# nintendac_mini.net
KiCad netlist of a schematic drawn in EAGLE
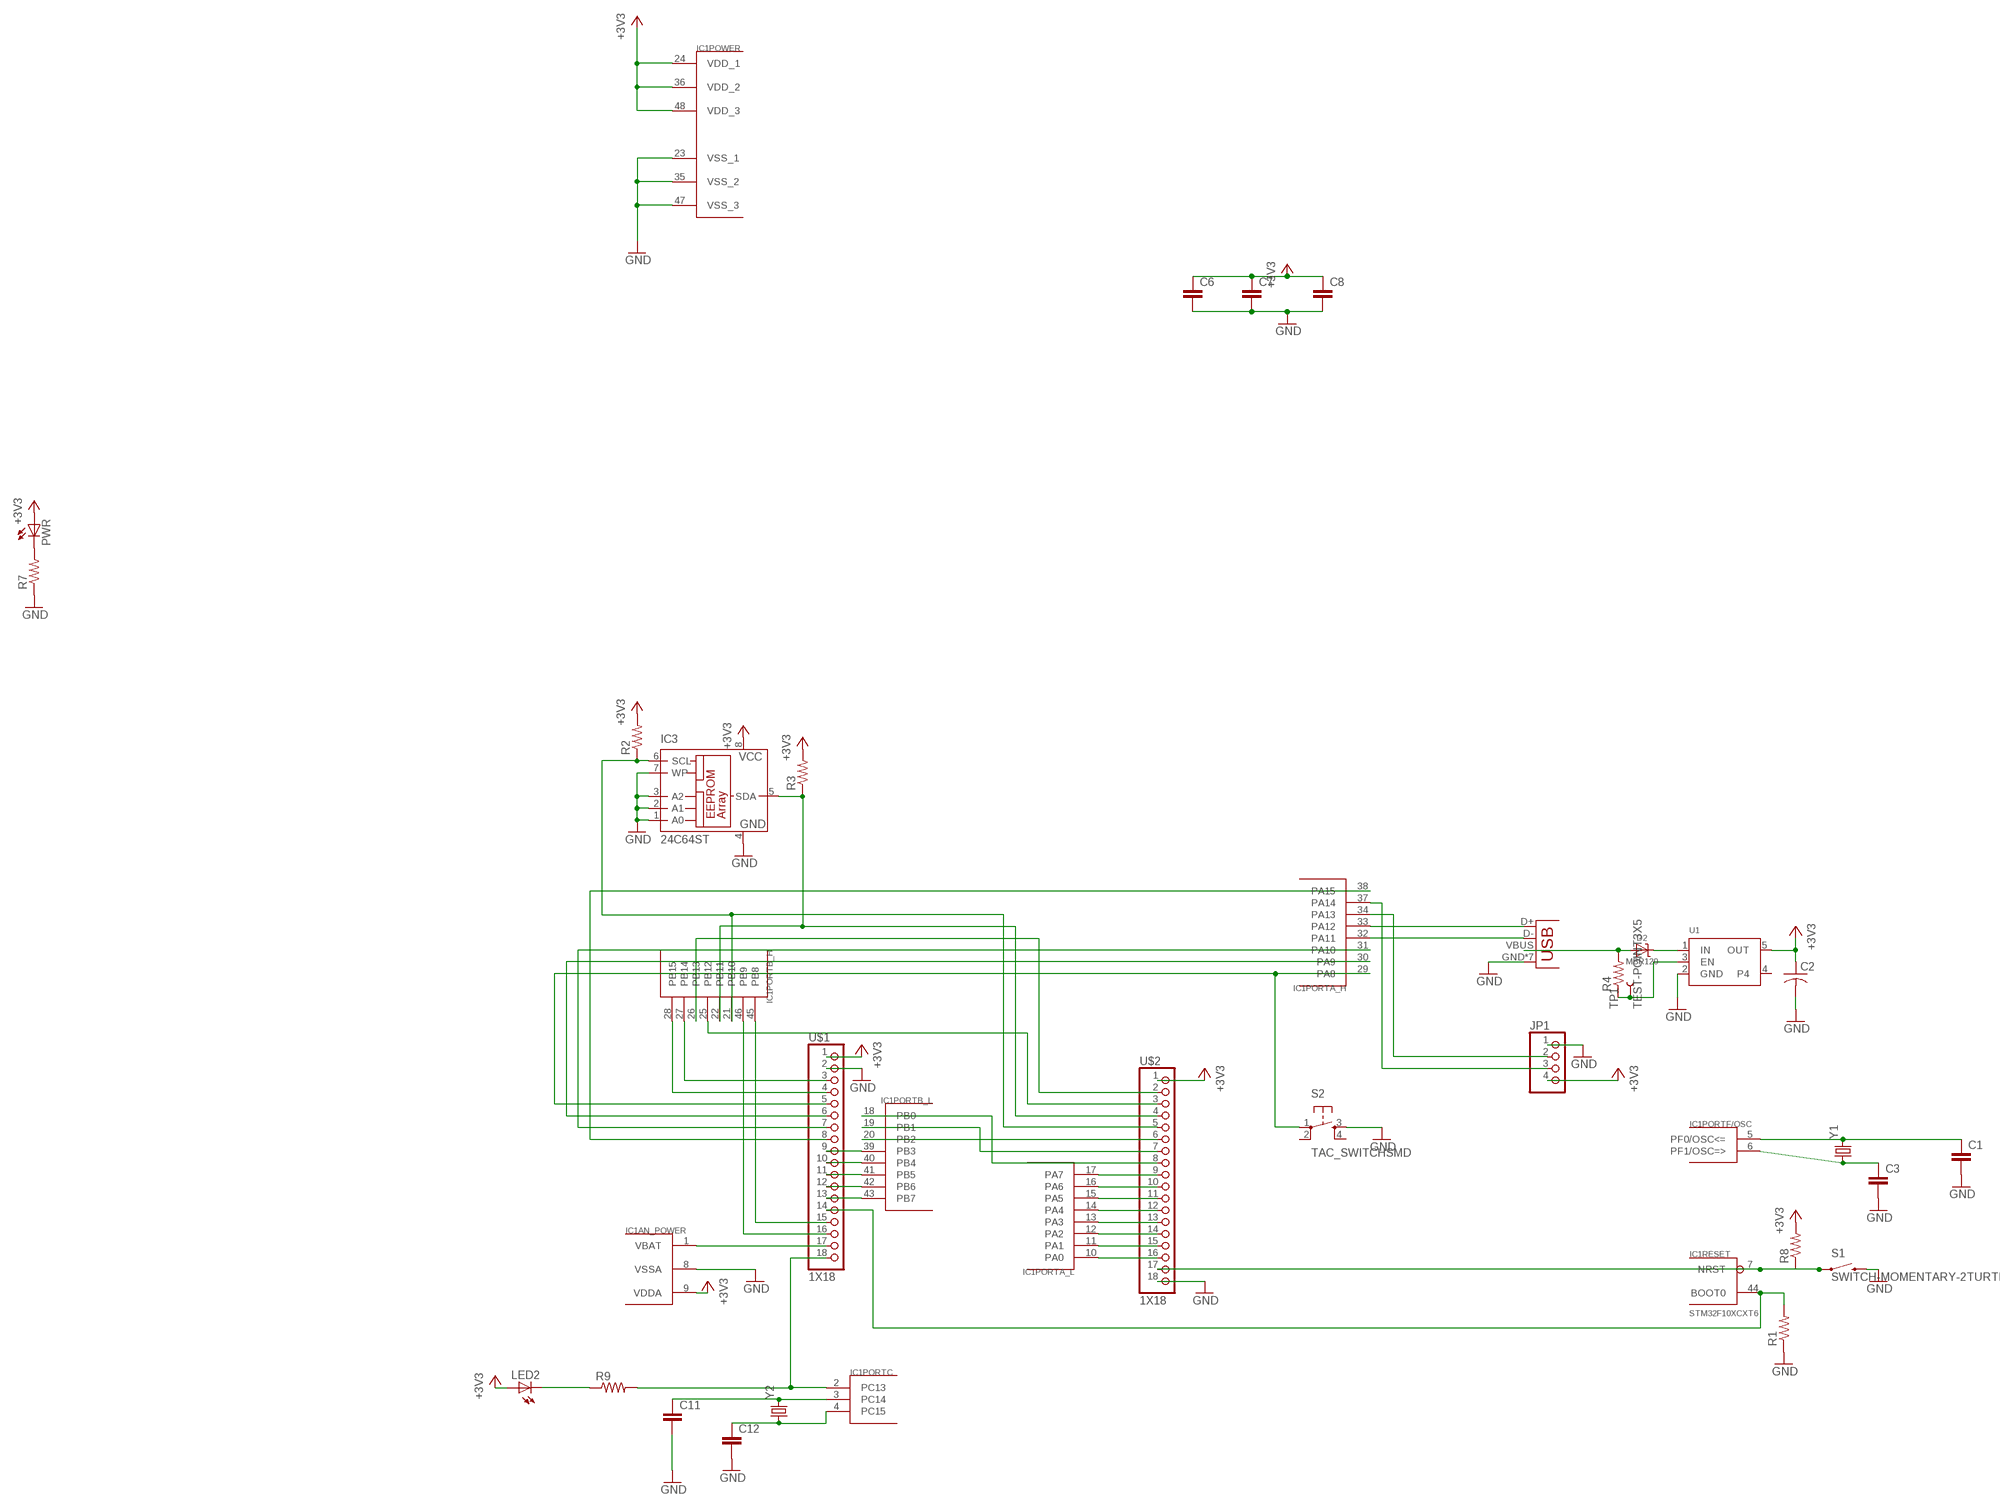
[diagram p0: schematic, sheet 1]

(export (version "E")
  (design (tool "Eeschema 10.0.6"))
  (components
    (comp (ref "C1")
      (value "CAP0805")
      (footprint "eagle-import:0805")
      (libsource (lib "eagle-import") (part "CAP0805"))
    )
    (comp (ref "C2")
      (value "C-USC1210")
      (footprint "eagle-import:C1210")
      (libsource (lib "eagle-import") (part "C-USC1210"))
    )
    (comp (ref "C3")
      (value "CAP0805")
      (footprint "eagle-import:0805")
      (libsource (lib "eagle-import") (part "CAP0805"))
    )
    (comp (ref "C6")
      (value "CAP0805")
      (footprint "eagle-import:0805")
      (libsource (lib "eagle-import") (part "CAP0805"))
    )
    (comp (ref "C7")
      (value "CAP0805")
      (footprint "eagle-import:0805")
      (libsource (lib "eagle-import") (part "CAP0805"))
    )
    (comp (ref "C8")
      (value "CAP0805")
      (footprint "eagle-import:0805")
      (libsource (lib "eagle-import") (part "CAP0805"))
    )
    (comp (ref "C11")
      (value "CAP0805")
      (footprint "eagle-import:0805")
      (libsource (lib "eagle-import") (part "CAP0805"))
    )
    (comp (ref "C12")
      (value "CAP0805")
      (footprint "eagle-import:0805")
      (libsource (lib "eagle-import") (part "CAP0805"))
    )
    (comp (ref "D2")
      (value "MBR120")
      (footprint "eagle-import:SOD-123")
      (libsource (lib "eagle-import") (part "DIODE-SCHOTTKYSOD-123"))
    )
    (comp (ref "IC1")
      (value "STM32F10XCXT6")
      (footprint "eagle-import:TQFP48")
      (libsource (lib "eagle-import") (part "STM32F10XCXT6"))
    )
    (comp (ref "IC3")
      (value "24C64ST")
      (footprint "eagle-import:TSSOP8")
      (fields (field (name "MPN") "CAT24C64YI-GT3"))
      (libsource (lib "eagle-import") (part "24STC64"))
    )
    (comp (ref "JP1")
      (value "PINHD-1X4")
      (footprint "eagle-import:1X04")
      (libsource (lib "eagle-import") (part "PINHD-1X4"))
    )
    (comp (ref "LED2")
      (value "LEDCHIP-LED0805")
      (footprint "eagle-import:CHIP-LED0805")
      (libsource (lib "eagle-import") (part "LEDCHIP-LED0805"))
    )
    (comp (ref "PWR")
      (value "LEDCHIP-LED0805")
      (footprint "eagle-import:CHIP-LED0805")
      (libsource (lib "eagle-import") (part "LEDCHIP-LED0805"))
    )
    (comp (ref "R1")
      (value "RESISTOR0805-RES")
      (footprint "eagle-import:0805")
      (libsource (lib "eagle-import") (part "RESISTOR0805-RES"))
    )
    (comp (ref "R2")
      (value "RESISTOR0805-RES")
      (footprint "eagle-import:0805")
      (libsource (lib "eagle-import") (part "RESISTOR0805-RES"))
    )
    (comp (ref "R3")
      (value "RESISTOR0805-RES")
      (footprint "eagle-import:0805")
      (libsource (lib "eagle-import") (part "RESISTOR0805-RES"))
    )
    (comp (ref "R4")
      (value "RESISTOR0805-RES")
      (footprint "eagle-import:0805")
      (libsource (lib "eagle-import") (part "RESISTOR0805-RES"))
    )
    (comp (ref "R7")
      (value "RESISTOR0805-RES")
      (footprint "eagle-import:0805")
      (libsource (lib "eagle-import") (part "RESISTOR0805-RES"))
    )
    (comp (ref "R8")
      (value "RESISTOR0805-RES")
      (footprint "eagle-import:0805")
      (libsource (lib "eagle-import") (part "RESISTOR0805-RES"))
    )
    (comp (ref "R9")
      (value "RESISTOR0805-RES")
      (footprint "eagle-import:0805")
      (libsource (lib "eagle-import") (part "RESISTOR0805-RES"))
    )
    (comp (ref "S1")
      (value "SWITCH-MOMENTARY-2TURTLE")
      (footprint "eagle-import:KMR2")
      (libsource (lib "eagle-import") (part "SWITCH-MOMENTARY-2TURTLE"))
    )
    (comp (ref "S2")
      (value "TAC_SWITCHSMD")
      (footprint "eagle-import:TACTILE-SWITCH-SMD")
      (libsource (lib "eagle-import") (part "TAC_SWITCHSMD"))
    )
    (comp (ref "TP1")
      (value "TEST-POINT3X5")
      (footprint "eagle-import:PAD.03X.05")
      (libsource (lib "eagle-import") (part "TEST-POINT3X5"))
    )
    (comp (ref "U$1")
      (value "1X18")
      (footprint "eagle-import:1X18")
      (libsource (lib "eagle-import") (part "1X18"))
    )
    (comp (ref "U$2")
      (value "1X18")
      (footprint "eagle-import:1X18")
      (libsource (lib "eagle-import") (part "1X18"))
    )
    (comp (ref "U1")
      (value "VREG_SOT23-5")
      (footprint "eagle-import:SOT23-5")
      (libsource (lib "eagle-import") (part "VREG_SOT23-5"))
    )
    (comp (ref "X1")
      (value "USB-MICROB")
      (footprint "eagle-import:USB-MICROB")
      (libsource (lib "eagle-import") (part "USB-MICROB"))
    )
    (comp (ref "Y1")
      (value "CRYSTALHC49US")
      (footprint "eagle-import:HC49US")
      (libsource (lib "eagle-import") (part "CRYSTALHC49US"))
    )
    (comp (ref "Y2")
      (value "CRYSTALTC26H_EZ")
      (footprint "eagle-import:TC26HEZ")
      (libsource (lib "eagle-import") (part "CRYSTALTC26H_EZ"))
    )
  )
  (nets
    (net (code "1") (name "+3V3") (class "Default")
      (node (ref "C2") (pin "1") (pinfunction "1_1") (pintype "passive"))
      (node (ref "C6") (pin "1") (pinfunction "1_1") (pintype "passive"))
      (node (ref "C7") (pin "1") (pinfunction "1_1") (pintype "passive"))
      (node (ref "C8") (pin "1") (pinfunction "1_1") (pintype "passive"))
      (node (ref "IC1") (pin "24") (pinfunction "VDD_1_24") (pintype "power_in"))
      (node (ref "IC1") (pin "36") (pinfunction "VDD_2_36") (pintype "power_in"))
      (node (ref "IC1") (pin "48") (pinfunction "VDD_3_48") (pintype "power_in"))
      (node (ref "IC1") (pin "9") (pinfunction "VDDA_9") (pintype "power_in"))
      (node (ref "IC3") (pin "8") (pinfunction "VCC_8") (pintype "power_in"))
      (node (ref "JP1") (pin "4") (pinfunction "4_4") (pintype "passive"))
      (node (ref "LED2") (pin "A") (pinfunction "A_A") (pintype "passive"))
      (node (ref "PWR") (pin "A") (pinfunction "A_A") (pintype "passive"))
      (node (ref "R2") (pin "2") (pinfunction "2_2") (pintype "passive"))
      (node (ref "R3") (pin "2") (pinfunction "2_2") (pintype "passive"))
      (node (ref "R8") (pin "2") (pinfunction "2_2") (pintype "passive"))
      (node (ref "U$1") (pin "1") (pinfunction "1_1") (pintype "passive"))
      (node (ref "U$2") (pin "1") (pinfunction "1_1") (pintype "passive"))
      (node (ref "U1") (pin "5") (pinfunction "OUT_5") (pintype "power_in"))
    )
    (net (code "2") (name "GND") (class "Default")
      (node (ref "C1") (pin "2") (pinfunction "2_2") (pintype "passive"))
      (node (ref "C11") (pin "2") (pinfunction "2_2") (pintype "passive"))
      (node (ref "C12") (pin "2") (pinfunction "2_2") (pintype "passive"))
      (node (ref "C2") (pin "2") (pinfunction "2_2") (pintype "passive"))
      (node (ref "C3") (pin "2") (pinfunction "2_2") (pintype "passive"))
      (node (ref "C6") (pin "2") (pinfunction "2_2") (pintype "passive"))
      (node (ref "C7") (pin "2") (pinfunction "2_2") (pintype "passive"))
      (node (ref "C8") (pin "2") (pinfunction "2_2") (pintype "passive"))
      (node (ref "IC1") (pin "23") (pinfunction "VSS_1_23") (pintype "power_in"))
      (node (ref "IC1") (pin "35") (pinfunction "VSS_2_35") (pintype "power_in"))
      (node (ref "IC1") (pin "47") (pinfunction "VSS_3_47") (pintype "power_in"))
      (node (ref "IC1") (pin "8") (pinfunction "VSSA_8") (pintype "power_in"))
      (node (ref "IC3") (pin "1") (pinfunction "A0_1") (pintype "input"))
      (node (ref "IC3") (pin "2") (pinfunction "A1_2") (pintype "input"))
      (node (ref "IC3") (pin "3") (pinfunction "A2_3") (pintype "input"))
      (node (ref "IC3") (pin "4") (pinfunction "GND_4") (pintype "power_in"))
      (node (ref "IC3") (pin "7") (pinfunction "WP_7") (pintype "input"))
      (node (ref "JP1") (pin "1") (pinfunction "1_1") (pintype "passive"))
      (node (ref "R1") (pin "1") (pinfunction "1_1") (pintype "passive"))
      (node (ref "R7") (pin "1") (pinfunction "1_1") (pintype "passive"))
      (node (ref "S1") (pin "3") (pinfunction "2_3") (pintype "passive"))
      (node (ref "S2") (pin "3") (pinfunction "3_3") (pintype "passive"))
      (node (ref "U$1") (pin "2") (pinfunction "2_2") (pintype "passive"))
      (node (ref "U$2") (pin "18") (pinfunction "18_18") (pintype "passive"))
      (node (ref "U1") (pin "2") (pinfunction "GND_2") (pintype "power_in"))
      (node (ref "X1") (pin "GND") (pinfunction "GND_GND") (pintype "bidirectional"))
      (node (ref "X1") (pin "P1") (pinfunction "GND_P1") (pintype "bidirectional"))
      (node (ref "X1") (pin "P2") (pinfunction "GND_P2") (pintype "bidirectional"))
      (node (ref "X1") (pin "P3") (pinfunction "GND_P3") (pintype "bidirectional"))
      (node (ref "X1") (pin "P4") (pinfunction "GND_P4") (pintype "bidirectional"))
      (node (ref "X1") (pin "P5") (pinfunction "GND_P5") (pintype "bidirectional"))
      (node (ref "X1") (pin "P6") (pinfunction "GND_P6") (pintype "bidirectional"))
    )
    (net (code "3") (name "Net-(D2-PadA)") (class "Default")
      (node (ref "D2") (pin "A") (pinfunction "A_A") (pintype "passive"))
      (node (ref "R4") (pin "2") (pinfunction "2_2") (pintype "passive"))
      (node (ref "X1") (pin "VBUS") (pinfunction "VBUS_VBUS") (pintype "bidirectional"))
    )
    (net (code "4") (name "Net-(IC1A-VBAT)") (class "Default")
      (node (ref "IC1") (pin "1") (pinfunction "VBAT_1") (pintype "power_in"))
      (node (ref "U$1") (pin "17") (pinfunction "17_17") (pintype "passive"))
    )
    (net (code "5") (name "Net-(IC1B-PA8)") (class "Default")
      (node (ref "IC1") (pin "29") (pinfunction "PA8_29") (pintype "bidirectional"))
      (node (ref "S2") (pin "1") (pinfunction "1_1") (pintype "passive"))
      (node (ref "U$1") (pin "5") (pinfunction "5_5") (pintype "passive"))
    )
    (net (code "6") (name "Net-(IC1B-PA9)") (class "Default")
      (node (ref "IC1") (pin "30") (pinfunction "PA9_30") (pintype "bidirectional"))
      (node (ref "U$1") (pin "6") (pinfunction "6_6") (pintype "passive"))
    )
    (net (code "7") (name "Net-(IC1B-PA10)") (class "Default")
      (node (ref "IC1") (pin "31") (pinfunction "PA10_31") (pintype "bidirectional"))
      (node (ref "U$1") (pin "7") (pinfunction "7_7") (pintype "passive"))
    )
    (net (code "8") (name "Net-(IC1B-PA11)") (class "Default")
      (node (ref "IC1") (pin "32") (pinfunction "PA11_32") (pintype "bidirectional"))
      (node (ref "X1") (pin "D-") (pinfunction "D-_D-") (pintype "bidirectional"))
    )
    (net (code "9") (name "Net-(IC1B-PA12)") (class "Default")
      (node (ref "IC1") (pin "33") (pinfunction "PA12_33") (pintype "bidirectional"))
      (node (ref "X1") (pin "D+") (pinfunction "D+_D+") (pintype "bidirectional"))
    )
    (net (code "10") (name "Net-(IC1B-PA13)") (class "Default")
      (node (ref "IC1") (pin "34") (pinfunction "PA13_34") (pintype "bidirectional"))
      (node (ref "JP1") (pin "2") (pinfunction "2_2") (pintype "passive"))
    )
    (net (code "11") (name "Net-(IC1B-PA14)") (class "Default")
      (node (ref "IC1") (pin "37") (pinfunction "PA14_37") (pintype "bidirectional"))
      (node (ref "JP1") (pin "3") (pinfunction "3_3") (pintype "passive"))
    )
    (net (code "12") (name "Net-(IC1B-PA15)") (class "Default")
      (node (ref "IC1") (pin "38") (pinfunction "PA15_38") (pintype "bidirectional"))
      (node (ref "U$1") (pin "8") (pinfunction "8_8") (pintype "passive"))
    )
    (net (code "13") (name "Net-(IC1C-PA0)") (class "Default")
      (node (ref "IC1") (pin "10") (pinfunction "PA0_10") (pintype "bidirectional"))
      (node (ref "U$2") (pin "16") (pinfunction "16_16") (pintype "passive"))
    )
    (net (code "14") (name "Net-(IC1C-PA1)") (class "Default")
      (node (ref "IC1") (pin "11") (pinfunction "PA1_11") (pintype "bidirectional"))
      (node (ref "U$2") (pin "15") (pinfunction "15_15") (pintype "passive"))
    )
    (net (code "15") (name "Net-(IC1C-PA2)") (class "Default")
      (node (ref "IC1") (pin "12") (pinfunction "PA2_12") (pintype "bidirectional"))
      (node (ref "U$2") (pin "14") (pinfunction "14_14") (pintype "passive"))
    )
    (net (code "16") (name "Net-(IC1C-PA3)") (class "Default")
      (node (ref "IC1") (pin "13") (pinfunction "PA3_13") (pintype "bidirectional"))
      (node (ref "U$2") (pin "13") (pinfunction "13_13") (pintype "passive"))
    )
    (net (code "17") (name "Net-(IC1C-PA4)") (class "Default")
      (node (ref "IC1") (pin "14") (pinfunction "PA4_14") (pintype "bidirectional"))
      (node (ref "U$2") (pin "12") (pinfunction "12_12") (pintype "passive"))
    )
    (net (code "18") (name "Net-(IC1C-PA5)") (class "Default")
      (node (ref "IC1") (pin "15") (pinfunction "PA5_15") (pintype "bidirectional"))
      (node (ref "U$2") (pin "11") (pinfunction "11_11") (pintype "passive"))
    )
    (net (code "19") (name "Net-(IC1C-PA6)") (class "Default")
      (node (ref "IC1") (pin "16") (pinfunction "PA6_16") (pintype "bidirectional"))
      (node (ref "U$2") (pin "10") (pinfunction "10_10") (pintype "passive"))
    )
    (net (code "20") (name "Net-(IC1C-PA7)") (class "Default")
      (node (ref "IC1") (pin "17") (pinfunction "PA7_17") (pintype "bidirectional"))
      (node (ref "U$2") (pin "9") (pinfunction "9_9") (pintype "passive"))
    )
    (net (code "21") (name "Net-(IC1D-PB8)") (class "Default")
      (node (ref "IC1") (pin "45") (pinfunction "PB8_45") (pintype "bidirectional"))
      (node (ref "U$1") (pin "15") (pinfunction "15_15") (pintype "passive"))
    )
    (net (code "22") (name "Net-(IC1D-PB9)") (class "Default")
      (node (ref "IC1") (pin "46") (pinfunction "PB9_46") (pintype "bidirectional"))
      (node (ref "U$1") (pin "16") (pinfunction "16_16") (pintype "passive"))
    )
    (net (code "23") (name "Net-(IC1D-PB10)") (class "Default")
      (node (ref "IC1") (pin "21") (pinfunction "PB10_21") (pintype "bidirectional"))
      (node (ref "IC3") (pin "6") (pinfunction "SCL_6") (pintype "input"))
      (node (ref "R2") (pin "1") (pinfunction "1_1") (pintype "passive"))
      (node (ref "U$2") (pin "5") (pinfunction "5_5") (pintype "passive"))
    )
    (net (code "24") (name "Net-(IC1D-PB11)") (class "Default")
      (node (ref "IC1") (pin "22") (pinfunction "PB11_22") (pintype "bidirectional"))
      (node (ref "IC3") (pin "5") (pinfunction "SDA_5") (pintype "bidirectional"))
      (node (ref "R3") (pin "1") (pinfunction "1_1") (pintype "passive"))
      (node (ref "U$2") (pin "4") (pinfunction "4_4") (pintype "passive"))
    )
    (net (code "25") (name "Net-(IC1D-PB12)") (class "Default")
      (node (ref "IC1") (pin "25") (pinfunction "PB12_25") (pintype "bidirectional"))
      (node (ref "U$2") (pin "3") (pinfunction "3_3") (pintype "passive"))
    )
    (net (code "26") (name "Net-(IC1D-PB13)") (class "Default")
      (node (ref "IC1") (pin "26") (pinfunction "PB13_26") (pintype "bidirectional"))
      (node (ref "U$2") (pin "2") (pinfunction "2_2") (pintype "passive"))
    )
    (net (code "27") (name "Net-(IC1D-PB14)") (class "Default")
      (node (ref "IC1") (pin "27") (pinfunction "PB14_27") (pintype "bidirectional"))
      (node (ref "U$1") (pin "3") (pinfunction "3_3") (pintype "passive"))
    )
    (net (code "28") (name "Net-(IC1D-PB15)") (class "Default")
      (node (ref "IC1") (pin "28") (pinfunction "PB15_28") (pintype "bidirectional"))
      (node (ref "U$1") (pin "4") (pinfunction "4_4") (pintype "passive"))
    )
    (net (code "29") (name "Net-(IC1E-PB0)") (class "Default")
      (node (ref "IC1") (pin "18") (pinfunction "PB0_18") (pintype "bidirectional"))
      (node (ref "U$2") (pin "8") (pinfunction "8_8") (pintype "passive"))
    )
    (net (code "30") (name "Net-(IC1E-PB1)") (class "Default")
      (node (ref "IC1") (pin "19") (pinfunction "PB1_19") (pintype "bidirectional"))
      (node (ref "U$2") (pin "7") (pinfunction "7_7") (pintype "passive"))
    )
    (net (code "31") (name "Net-(IC1E-PB2)") (class "Default")
      (node (ref "IC1") (pin "20") (pinfunction "PB2_20") (pintype "bidirectional"))
      (node (ref "U$2") (pin "6") (pinfunction "6_6") (pintype "passive"))
    )
    (net (code "32") (name "Net-(IC1E-PB3)") (class "Default")
      (node (ref "IC1") (pin "39") (pinfunction "PB3_39") (pintype "bidirectional"))
      (node (ref "U$1") (pin "9") (pinfunction "9_9") (pintype "passive"))
    )
    (net (code "33") (name "Net-(IC1E-PB4)") (class "Default")
      (node (ref "IC1") (pin "40") (pinfunction "PB4_40") (pintype "bidirectional"))
      (node (ref "U$1") (pin "10") (pinfunction "10_10") (pintype "passive"))
    )
    (net (code "34") (name "Net-(IC1E-PB5)") (class "Default")
      (node (ref "IC1") (pin "41") (pinfunction "PB5_41") (pintype "bidirectional"))
      (node (ref "U$1") (pin "11") (pinfunction "11_11") (pintype "passive"))
    )
    (net (code "35") (name "Net-(IC1E-PB6)") (class "Default")
      (node (ref "IC1") (pin "42") (pinfunction "PB6_42") (pintype "bidirectional"))
      (node (ref "U$1") (pin "12") (pinfunction "12_12") (pintype "passive"))
    )
    (net (code "36") (name "Net-(IC1E-PB7)") (class "Default")
      (node (ref "IC1") (pin "43") (pinfunction "PB7_43") (pintype "bidirectional"))
      (node (ref "U$1") (pin "13") (pinfunction "13_13") (pintype "passive"))
    )
    (net (code "37") (name "Net-(IC1F-PC13)") (class "Default")
      (node (ref "IC1") (pin "2") (pinfunction "PC13_2") (pintype "bidirectional"))
      (node (ref "R9") (pin "2") (pinfunction "2_2") (pintype "passive"))
      (node (ref "U$1") (pin "18") (pinfunction "18_18") (pintype "passive"))
    )
    (net (code "38") (name "Net-(IC1F-PC14)") (class "Default")
      (node (ref "C11") (pin "1") (pinfunction "1_1") (pintype "passive"))
      (node (ref "IC1") (pin "3") (pinfunction "PC14_3") (pintype "bidirectional"))
      (node (ref "Y2") (pin "2") (pinfunction "2_2") (pintype "passive"))
    )
    (net (code "39") (name "Net-(IC1F-PC15)") (class "Default")
      (node (ref "C12") (pin "1") (pinfunction "1_1") (pintype "passive"))
      (node (ref "IC1") (pin "4") (pinfunction "PC15_4") (pintype "bidirectional"))
      (node (ref "Y2") (pin "1") (pinfunction "1_1") (pintype "passive"))
    )
    (net (code "40") (name "Net-(IC1G-PF0{slash}OSC<=)") (class "Default")
      (node (ref "C1") (pin "1") (pinfunction "1_1") (pintype "passive"))
      (node (ref "IC1") (pin "5") (pinfunction "PF0/OSC<=_5") (pintype "bidirectional"))
      (node (ref "Y1") (pin "2") (pinfunction "2_2") (pintype "passive"))
    )
    (net (code "41") (name "Net-(IC1G-PF1{slash}OSC=>)") (class "Default")
      (node (ref "C3") (pin "1") (pinfunction "1_1") (pintype "passive"))
      (node (ref "IC1") (pin "6") (pinfunction "PF1/OSC=>_6") (pintype "bidirectional"))
      (node (ref "Y1") (pin "1") (pinfunction "1_1") (pintype "passive"))
    )
    (net (code "42") (name "Net-(IC1I-BOOT0)") (class "Default")
      (node (ref "IC1") (pin "44") (pinfunction "BOOT0_44") (pintype "input"))
      (node (ref "R1") (pin "2") (pinfunction "2_2") (pintype "passive"))
      (node (ref "U$1") (pin "14") (pinfunction "14_14") (pintype "passive"))
    )
    (net (code "43") (name "Net-(IC1I-NRST)") (class "Default")
      (node (ref "IC1") (pin "7") (pinfunction "NRST_7") (pintype "input"))
      (node (ref "R8") (pin "1") (pinfunction "1_1") (pintype "passive"))
      (node (ref "S1") (pin "1") (pinfunction "1_1") (pintype "passive"))
      (node (ref "U$2") (pin "17") (pinfunction "17_17") (pintype "passive"))
    )
    (net (code "44") (name "Net-(LED2-PadC)") (class "Default")
      (node (ref "LED2") (pin "C") (pinfunction "C_C") (pintype "passive"))
      (node (ref "R9") (pin "1") (pinfunction "1_1") (pintype "passive"))
    )
    (net (code "45") (name "Net-(PWR-PadC)") (class "Default")
      (node (ref "PWR") (pin "C") (pinfunction "C_C") (pintype "passive"))
      (node (ref "R7") (pin "2") (pinfunction "2_2") (pintype "passive"))
    )
    (net (code "46") (name "Net-(TP1-1)") (class "Default")
      (node (ref "R4") (pin "1") (pinfunction "1_1") (pintype "passive"))
      (node (ref "TP1") (pin "P$1") (pinfunction "1_P$1") (pintype "bidirectional"))
      (node (ref "U1") (pin "3") (pinfunction "EN_3") (pintype "input"))
    )
    (net (code "47") (name "Net-(U1-IN)") (class "Default")
      (node (ref "D2") (pin "C") (pinfunction "C_C") (pintype "passive"))
      (node (ref "U1") (pin "1") (pinfunction "IN_1") (pintype "power_in"))
    )
    (net (code "48") (name "unconnected-(S2-Pad2)") (class "Default")
      (node (ref "S2") (pin "2") (pinfunction "2_2") (pintype "passive"))
    )
    (net (code "49") (name "unconnected-(S2-Pad4)") (class "Default")
      (node (ref "S2") (pin "4") (pinfunction "4_4") (pintype "passive"))
    )
    (net (code "50") (name "unconnected-(U1-P4-Pad4)") (class "Default")
      (node (ref "U1") (pin "4") (pinfunction "P4_4") (pintype "bidirectional"))
    )
  )
)
